# r10_328_1284.net
KiCad netlist of a schematic drawn in EAGLE
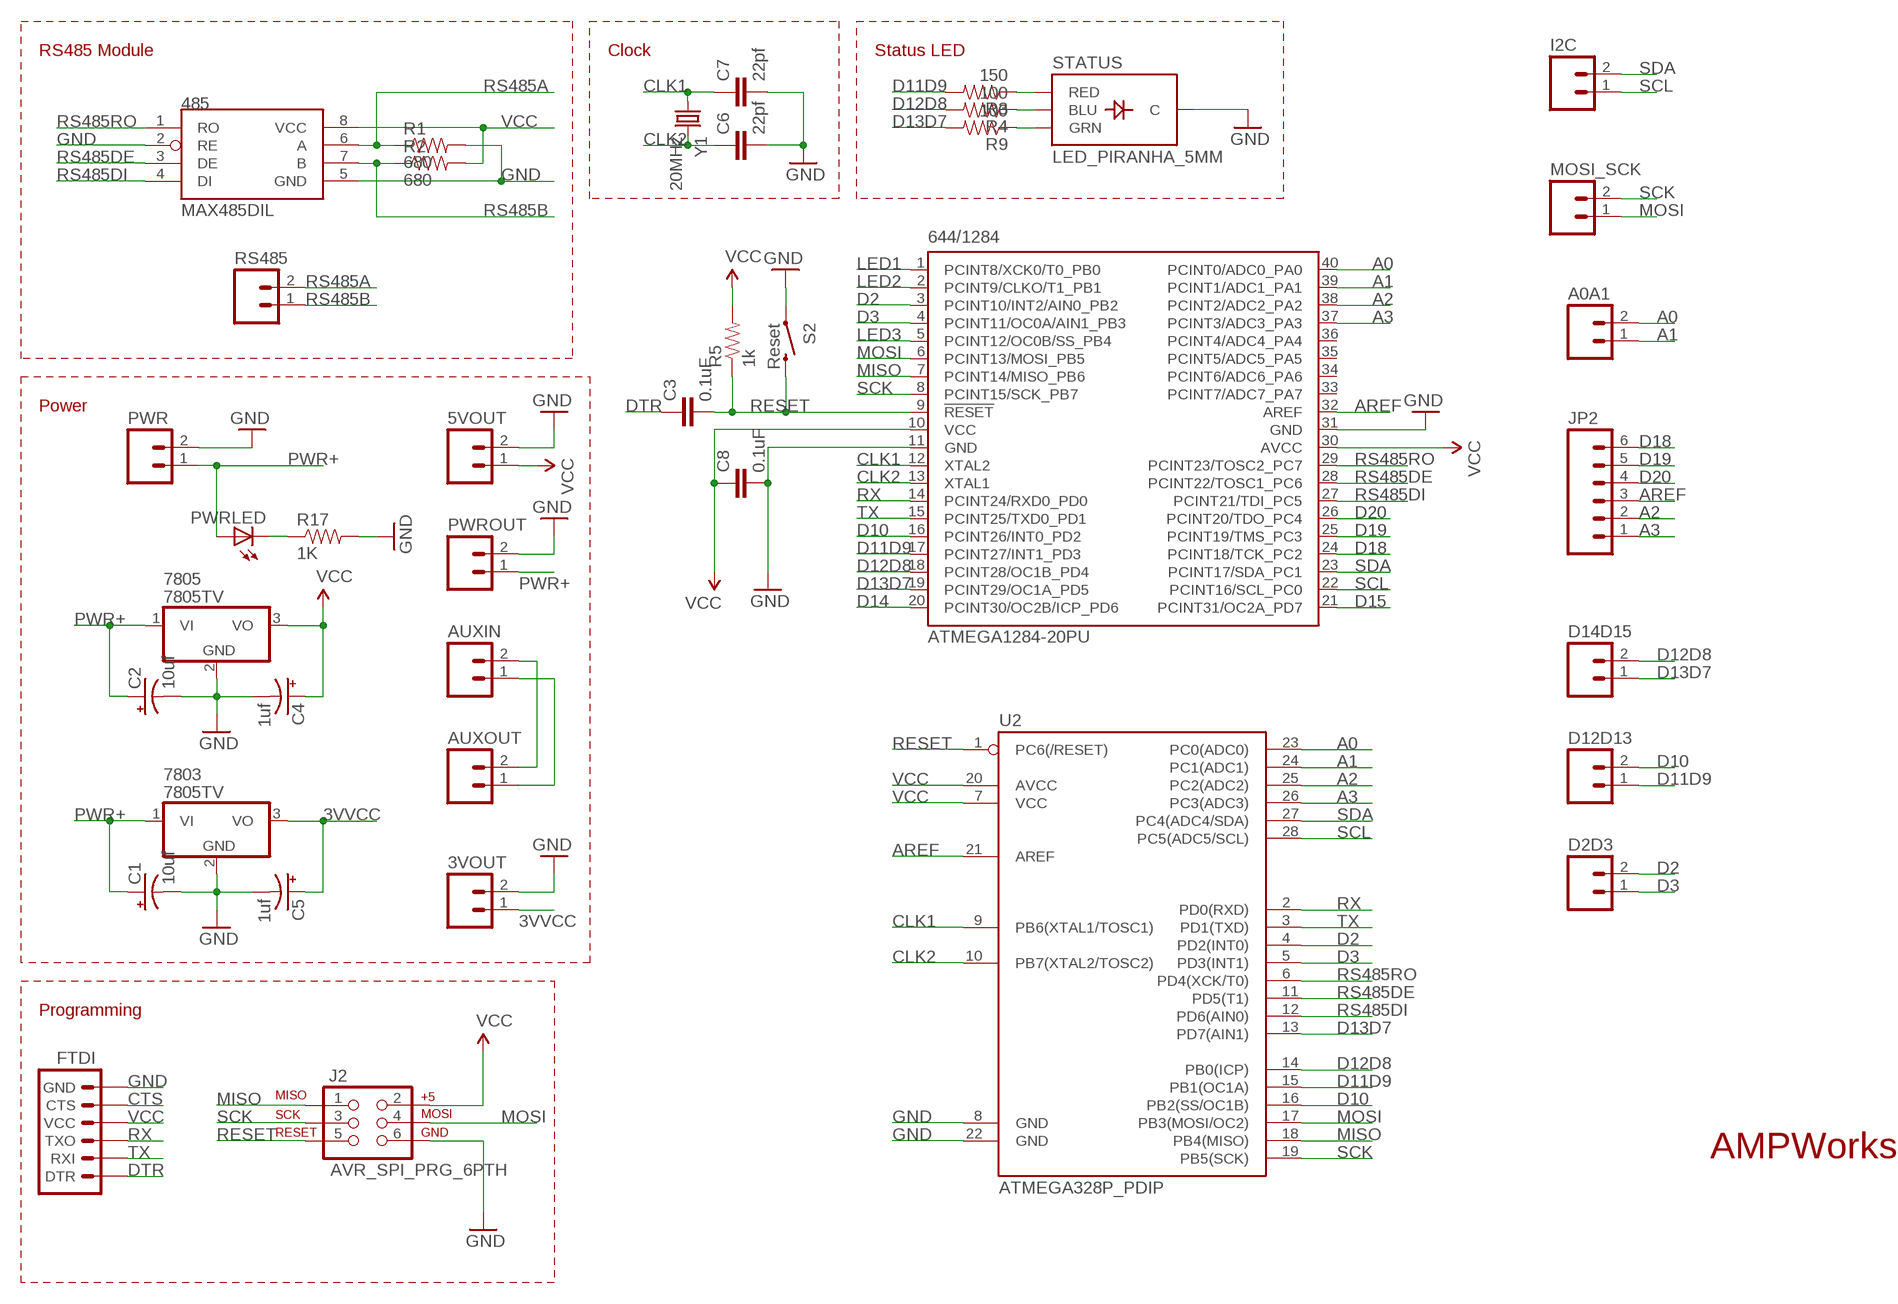
[diagram p0: schematic, sheet 1]

(export (version "E")
  (design (tool "Eeschema 10.0.6"))
  (components
    (comp (ref "3VOUT")
      (value "M025MM")
      (footprint "eagle-import:SCREWTERMINAL-5MM-2")
      (libsource (lib "eagle-import") (part "M025MM"))
    )
    (comp (ref "5VOUT")
      (value "M025MM")
      (footprint "eagle-import:SCREWTERMINAL-5MM-2")
      (libsource (lib "eagle-import") (part "M025MM"))
    )
    (comp (ref "485")
      (value "MAX485DIL")
      (footprint "eagle-import:DIL08")
      (libsource (lib "eagle-import") (part "MAX485DIL"))
    )
    (comp (ref "644/1284")
      (value "ATMEGA1284-20PU")
      (footprint "eagle-import:DIL40")
      (fields (field (name "MPN") "ATMEGA644-20PU"))
      (libsource (lib "eagle-import") (part "ATMEGA644-PU20"))
    )
    (comp (ref "7803")
      (value "7805TV")
      (footprint "eagle-import:TO220V")
      (libsource (lib "eagle-import") (part "78TV05"))
    )
    (comp (ref "7805")
      (value "7805TV")
      (footprint "eagle-import:TO220V")
      (libsource (lib "eagle-import") (part "78TV05"))
    )
    (comp (ref "A0A1")
      (value "M025MM")
      (footprint "eagle-import:SCREWTERMINAL-5MM-2")
      (libsource (lib "eagle-import") (part "M025MM"))
    )
    (comp (ref "AUXIN")
      (value "M025MM")
      (footprint "eagle-import:SCREWTERMINAL-5MM-2")
      (libsource (lib "eagle-import") (part "M025MM"))
    )
    (comp (ref "AUXOUT")
      (value "M025MM")
      (footprint "eagle-import:SCREWTERMINAL-5MM-2")
      (libsource (lib "eagle-import") (part "M025MM"))
    )
    (comp (ref "C1")
      (value "10uf")
      (footprint "eagle-import:CPOL-RADIAL-10UF-25V")
      (libsource (lib "eagle-import") (part "CAP_POLPTH2"))
    )
    (comp (ref "C2")
      (value "10uf")
      (footprint "eagle-import:CPOL-RADIAL-10UF-25V")
      (libsource (lib "eagle-import") (part "CAP_POLPTH2"))
    )
    (comp (ref "C3")
      (value "0.1uF")
      (footprint "eagle-import:CAP-PTH-SMALL")
      (libsource (lib "eagle-import") (part "CAPPTH"))
    )
    (comp (ref "C4")
      (value "1uf")
      (footprint "eagle-import:CPOL-RADIAL-10UF-25V")
      (libsource (lib "eagle-import") (part "CAP_POLPTH2"))
    )
    (comp (ref "C5")
      (value "1uf")
      (footprint "eagle-import:CPOL-RADIAL-10UF-25V")
      (libsource (lib "eagle-import") (part "CAP_POLPTH2"))
    )
    (comp (ref "C6")
      (value "22pf")
      (footprint "eagle-import:CAP-PTH-SMALL")
      (libsource (lib "eagle-import") (part "CAPPTH"))
    )
    (comp (ref "C7")
      (value "22pf")
      (footprint "eagle-import:CAP-PTH-SMALL")
      (libsource (lib "eagle-import") (part "CAPPTH"))
    )
    (comp (ref "C8")
      (value "0.1uF")
      (footprint "eagle-import:CAP-PTH-SMALL")
      (libsource (lib "eagle-import") (part "CAPPTH"))
    )
    (comp (ref "D2D3")
      (value "M025MM")
      (footprint "eagle-import:SCREWTERMINAL-5MM-2")
      (libsource (lib "eagle-import") (part "M025MM"))
    )
    (comp (ref "D12D13")
      (value "M025MM")
      (footprint "eagle-import:SCREWTERMINAL-5MM-2")
      (libsource (lib "eagle-import") (part "M025MM"))
    )
    (comp (ref "D14D15")
      (value "M025MM")
      (footprint "eagle-import:SCREWTERMINAL-5MM-2")
      (libsource (lib "eagle-import") (part "M025MM"))
    )
    (comp (ref "FTDI")
      (value "ARDUINO_SERIAL_PROGRAMPTH")
      (footprint "eagle-import:1X06")
      (libsource (lib "eagle-import") (part "ARDUINO_SERIAL_PROGRAMPTH"))
    )
    (comp (ref "I2C")
      (value "M025MM")
      (footprint "eagle-import:SCREWTERMINAL-5MM-2")
      (libsource (lib "eagle-import") (part "M025MM"))
    )
    (comp (ref "J2")
      (value "AVR_SPI_PRG_6PTH")
      (footprint "eagle-import:2X3")
      (libsource (lib "eagle-import") (part "AVR_SPI_PRG_6PTH"))
    )
    (comp (ref "JP2")
      (value "M06NO_SILK")
      (footprint "eagle-import:1X06_NO_SILK")
      (libsource (lib "eagle-import") (part "M06NO_SILK"))
    )
    (comp (ref "MOSI_SCK")
      (value "M025MM")
      (footprint "eagle-import:SCREWTERMINAL-5MM-2")
      (libsource (lib "eagle-import") (part "M025MM"))
    )
    (comp (ref "PWR")
      (value "M025MM")
      (footprint "eagle-import:SCREWTERMINAL-5MM-2")
      (libsource (lib "eagle-import") (part "M025MM"))
    )
    (comp (ref "PWRLED")
      (value "LED5MM")
      (footprint "eagle-import:LED5MM")
      (libsource (lib "eagle-import") (part "LED5MM"))
    )
    (comp (ref "PWROUT")
      (value "M025MM")
      (footprint "eagle-import:SCREWTERMINAL-5MM-2")
      (libsource (lib "eagle-import") (part "M025MM"))
    )
    (comp (ref "R1")
      (value "680")
      (footprint "eagle-import:AXIAL-0.4")
      (libsource (lib "eagle-import") (part "SparkFun-Resistors_RESISTORPTH-1/4W"))
    )
    (comp (ref "R2")
      (value "680")
      (footprint "eagle-import:AXIAL-0.4")
      (libsource (lib "eagle-import") (part "SparkFun-Resistors_RESISTORPTH-1/4W"))
    )
    (comp (ref "R3")
      (value "150")
      (footprint "eagle-import:AXIAL-0.4")
      (libsource (lib "eagle-import") (part "RESISTORPTH-1/4W"))
    )
    (comp (ref "R4")
      (value "100")
      (footprint "eagle-import:AXIAL-0.4")
      (libsource (lib "eagle-import") (part "RESISTORPTH-1/4W"))
    )
    (comp (ref "R5")
      (value "1k")
      (footprint "eagle-import:AXIAL-0.4")
      (libsource (lib "eagle-import") (part "RESISTORPTH-1/4W"))
    )
    (comp (ref "R9")
      (value "100")
      (footprint "eagle-import:AXIAL-0.4")
      (libsource (lib "eagle-import") (part "RESISTORPTH-1/4W"))
    )
    (comp (ref "R17")
      (value "1K")
      (footprint "eagle-import:AXIAL-0.4")
      (libsource (lib "eagle-import") (part "SparkFun-Resistors_RESISTORPTH-1/4W"))
    )
    (comp (ref "RS485")
      (value "M025MM")
      (footprint "eagle-import:SCREWTERMINAL-5MM-2")
      (libsource (lib "eagle-import") (part "M025MM"))
    )
    (comp (ref "S2")
      (value "Reset")
      (footprint "eagle-import:TACTILE_SWITCH_SMD")
      (libsource (lib "eagle-import") (part "SWITCH-MOMENTARY-2SMD"))
    )
    (comp (ref "STATUS")
      (value "LED_PIRANHA_5MM")
      (footprint "eagle-import:LED_PIRANHA_5MM")
      (libsource (lib "eagle-import") (part "LED_PIRANHA_5MM"))
    )
    (comp (ref "U2")
      (value "ATMEGA328P_PDIP")
      (footprint "eagle-import:DIL28-3")
      (libsource (lib "eagle-import") (part "ATMEGA328P_PDIP"))
    )
    (comp (ref "Y1")
      (value "20MHz")
      (footprint "eagle-import:HC49US")
      (libsource (lib "eagle-import") (part "CRYSTALHC49US"))
    )
  )
  (nets
    (net (code "1") (name "/3VVCC") (class "Default")
      (node (ref "3VOUT") (pin "1") (pinfunction "1_1") (pintype "passive"))
      (node (ref "7803") (pin "3") (pinfunction "VO_3") (pintype "passive"))
      (node (ref "C5") (pin "1") (pinfunction "+_1") (pintype "passive"))
    )
    (net (code "2") (name "/A0") (class "Default")
      (node (ref "644/1284") (pin "40") (pinfunction "PCINT0/ADC0_PA0_40") (pintype "bidirectional"))
      (node (ref "A0A1") (pin "2") (pinfunction "2_2") (pintype "passive"))
      (node (ref "U2") (pin "23") (pinfunction "PC0(ADC0)_23") (pintype "bidirectional"))
    )
    (net (code "3") (name "/A1") (class "Default")
      (node (ref "644/1284") (pin "39") (pinfunction "PCINT1/ADC1_PA1_39") (pintype "bidirectional"))
      (node (ref "A0A1") (pin "1") (pinfunction "1_1") (pintype "passive"))
      (node (ref "U2") (pin "24") (pinfunction "PC1(ADC1)_24") (pintype "bidirectional"))
    )
    (net (code "4") (name "/A2") (class "Default")
      (node (ref "644/1284") (pin "38") (pinfunction "PCINT2/ADC2_PA2_38") (pintype "bidirectional"))
      (node (ref "JP2") (pin "2") (pinfunction "2_2") (pintype "passive"))
      (node (ref "U2") (pin "25") (pinfunction "PC2(ADC2)_25") (pintype "bidirectional"))
    )
    (net (code "5") (name "/A3") (class "Default")
      (node (ref "644/1284") (pin "37") (pinfunction "PCINT3/ADC3_PA3_37") (pintype "bidirectional"))
      (node (ref "JP2") (pin "1") (pinfunction "1_1") (pintype "passive"))
      (node (ref "U2") (pin "26") (pinfunction "PC3(ADC3)_26") (pintype "bidirectional"))
    )
    (net (code "6") (name "/AREF") (class "Default")
      (node (ref "644/1284") (pin "32") (pinfunction "AREF_32") (pintype "passive"))
      (node (ref "JP2") (pin "3") (pinfunction "3_3") (pintype "passive"))
      (node (ref "U2") (pin "21") (pinfunction "AREF_21") (pintype "bidirectional"))
    )
    (net (code "7") (name "/CLK1") (class "Default")
      (node (ref "644/1284") (pin "12") (pinfunction "XTAL2_12") (pintype "output"))
      (node (ref "C7") (pin "1") (pinfunction "1_1") (pintype "passive"))
      (node (ref "U2") (pin "9") (pinfunction "PB6(XTAL1/TOSC1)_9") (pintype "bidirectional"))
      (node (ref "Y1") (pin "1") (pinfunction "1_1") (pintype "passive"))
    )
    (net (code "8") (name "/CLK2") (class "Default")
      (node (ref "644/1284") (pin "13") (pinfunction "XTAL1_13") (pintype "input"))
      (node (ref "C6") (pin "1") (pinfunction "1_1") (pintype "passive"))
      (node (ref "U2") (pin "10") (pinfunction "PB7(XTAL2/TOSC2)_10") (pintype "bidirectional"))
      (node (ref "Y1") (pin "2") (pinfunction "2_2") (pintype "passive"))
    )
    (net (code "9") (name "/CTS") (class "Default")
      (node (ref "FTDI") (pin "CTS") (pinfunction "CTS_CTS") (pintype "passive"))
    )
    (net (code "10") (name "/D2") (class "Default")
      (node (ref "644/1284") (pin "3") (pinfunction "PCINT10/INT2/AIN0_PB2_3") (pintype "bidirectional"))
      (node (ref "D2D3") (pin "2") (pinfunction "2_2") (pintype "passive"))
      (node (ref "U2") (pin "4") (pinfunction "PD2(INT0)_4") (pintype "bidirectional"))
    )
    (net (code "11") (name "/D3") (class "Default")
      (node (ref "644/1284") (pin "4") (pinfunction "PCINT11/OC0A/AIN1_PB3_4") (pintype "bidirectional"))
      (node (ref "D2D3") (pin "1") (pinfunction "1_1") (pintype "passive"))
      (node (ref "U2") (pin "5") (pinfunction "PD3(INT1)_5") (pintype "bidirectional"))
    )
    (net (code "12") (name "/D10") (class "Default")
      (node (ref "644/1284") (pin "16") (pinfunction "PCINT26/INT0_PD2_16") (pintype "bidirectional"))
      (node (ref "D12D13") (pin "2") (pinfunction "2_2") (pintype "passive"))
      (node (ref "U2") (pin "16") (pinfunction "PB2(SS/OC1B)_16") (pintype "bidirectional"))
    )
    (net (code "13") (name "/D11D9") (class "Default")
      (node (ref "644/1284") (pin "17") (pinfunction "PCINT27/INT1_PD3_17") (pintype "bidirectional"))
      (node (ref "D12D13") (pin "1") (pinfunction "1_1") (pintype "passive"))
      (node (ref "R3") (pin "P$2") (pinfunction "2_P$2") (pintype "passive"))
      (node (ref "U2") (pin "15") (pinfunction "PB1(OC1A)_15") (pintype "bidirectional"))
    )
    (net (code "14") (name "/D12D8") (class "Default")
      (node (ref "644/1284") (pin "18") (pinfunction "PCINT28/OC1B_PD4_18") (pintype "bidirectional"))
      (node (ref "D14D15") (pin "2") (pinfunction "2_2") (pintype "passive"))
      (node (ref "R4") (pin "P$2") (pinfunction "2_P$2") (pintype "passive"))
      (node (ref "U2") (pin "14") (pinfunction "PB0(ICP)_14") (pintype "bidirectional"))
    )
    (net (code "15") (name "/D13D7") (class "Default")
      (node (ref "644/1284") (pin "19") (pinfunction "PCINT29/OC1A_PD5_19") (pintype "bidirectional"))
      (node (ref "D14D15") (pin "1") (pinfunction "1_1") (pintype "passive"))
      (node (ref "R9") (pin "P$2") (pinfunction "2_P$2") (pintype "passive"))
      (node (ref "U2") (pin "13") (pinfunction "PD7(AIN1)_13") (pintype "bidirectional"))
    )
    (net (code "16") (name "/D14") (class "Default")
      (node (ref "644/1284") (pin "20") (pinfunction "PCINT30/OC2B/ICP_PD6_20") (pintype "bidirectional"))
    )
    (net (code "17") (name "/D15") (class "Default")
      (node (ref "644/1284") (pin "21") (pinfunction "PCINT31/OC2A_PD7_21") (pintype "bidirectional"))
    )
    (net (code "18") (name "/D18") (class "Default")
      (node (ref "644/1284") (pin "24") (pinfunction "PCINT18/TCK_PC2_24") (pintype "bidirectional"))
      (node (ref "JP2") (pin "6") (pinfunction "6_6") (pintype "passive"))
    )
    (net (code "19") (name "/D19") (class "Default")
      (node (ref "644/1284") (pin "25") (pinfunction "PCINT19/TMS_PC3_25") (pintype "bidirectional"))
      (node (ref "JP2") (pin "5") (pinfunction "5_5") (pintype "passive"))
    )
    (net (code "20") (name "/D20") (class "Default")
      (node (ref "644/1284") (pin "26") (pinfunction "PCINT20/TDO_PC4_26") (pintype "bidirectional"))
      (node (ref "JP2") (pin "4") (pinfunction "4_4") (pintype "passive"))
    )
    (net (code "21") (name "/DTR") (class "Default")
      (node (ref "C3") (pin "1") (pinfunction "1_1") (pintype "passive"))
      (node (ref "FTDI") (pin "DTR") (pinfunction "DTR_DTR") (pintype "passive"))
    )
    (net (code "22") (name "/LED1") (class "Default")
      (node (ref "644/1284") (pin "1") (pinfunction "PCINT8/XCK0/T0_PB0_1") (pintype "bidirectional"))
    )
    (net (code "23") (name "/LED2") (class "Default")
      (node (ref "644/1284") (pin "2") (pinfunction "PCINT9/CLKO/T1_PB1_2") (pintype "bidirectional"))
    )
    (net (code "24") (name "/LED3") (class "Default")
      (node (ref "644/1284") (pin "5") (pinfunction "PCINT12/OC0B/SS_PB4_5") (pintype "bidirectional"))
    )
    (net (code "25") (name "/MISO") (class "Default")
      (node (ref "644/1284") (pin "7") (pinfunction "PCINT14/MISO_PB6_7") (pintype "bidirectional"))
      (node (ref "J2") (pin "1") (pinfunction "1_1") (pintype "passive"))
      (node (ref "U2") (pin "18") (pinfunction "PB4(MISO)_18") (pintype "bidirectional"))
    )
    (net (code "26") (name "/MOSI") (class "Default")
      (node (ref "644/1284") (pin "6") (pinfunction "PCINT13/MOSI_PB5_6") (pintype "bidirectional"))
      (node (ref "J2") (pin "4") (pinfunction "4_4") (pintype "passive"))
      (node (ref "MOSI_SCK") (pin "1") (pinfunction "1_1") (pintype "passive"))
      (node (ref "U2") (pin "17") (pinfunction "PB3(MOSI/OC2)_17") (pintype "bidirectional"))
    )
    (net (code "27") (name "/PWR+") (class "Default")
      (node (ref "7803") (pin "1") (pinfunction "VI_1") (pintype "input"))
      (node (ref "7805") (pin "1") (pinfunction "VI_1") (pintype "input"))
      (node (ref "C1") (pin "1") (pinfunction "+_1") (pintype "passive"))
      (node (ref "C2") (pin "1") (pinfunction "+_1") (pintype "passive"))
      (node (ref "PWR") (pin "1") (pinfunction "1_1") (pintype "passive"))
      (node (ref "PWRLED") (pin "A") (pinfunction "A_A") (pintype "passive"))
      (node (ref "PWROUT") (pin "1") (pinfunction "1_1") (pintype "passive"))
    )
    (net (code "28") (name "/RESET") (class "Default")
      (node (ref "644/1284") (pin "9") (pinfunction "~{RESET}_9") (pintype "input"))
      (node (ref "C3") (pin "2") (pinfunction "2_2") (pintype "passive"))
      (node (ref "J2") (pin "5") (pinfunction "5_5") (pintype "passive"))
      (node (ref "R5") (pin "P$1") (pinfunction "1_P$1") (pintype "passive"))
      (node (ref "S2") (pin "3") (pinfunction "2_3") (pintype "passive"))
      (node (ref "U2") (pin "1") (pinfunction "PC6(/RESET)_1") (pintype "bidirectional"))
    )
    (net (code "29") (name "/RS485A") (class "Default")
      (node (ref "485") (pin "6") (pinfunction "A_6") (pintype "bidirectional"))
      (node (ref "R1") (pin "P$1") (pinfunction "1_P$1") (pintype "passive"))
      (node (ref "RS485") (pin "2") (pinfunction "2_2") (pintype "passive"))
    )
    (net (code "30") (name "/RS485B") (class "Default")
      (node (ref "485") (pin "7") (pinfunction "B_7") (pintype "bidirectional"))
      (node (ref "R2") (pin "P$1") (pinfunction "1_P$1") (pintype "passive"))
      (node (ref "RS485") (pin "1") (pinfunction "1_1") (pintype "passive"))
    )
    (net (code "31") (name "/RS485DE") (class "Default")
      (node (ref "485") (pin "3") (pinfunction "DE_3") (pintype "bidirectional"))
      (node (ref "644/1284") (pin "28") (pinfunction "PCINT22/TOSC1_PC6_28") (pintype "bidirectional"))
      (node (ref "U2") (pin "11") (pinfunction "PD5(T1)_11") (pintype "bidirectional"))
    )
    (net (code "32") (name "/RS485DI") (class "Default")
      (node (ref "485") (pin "4") (pinfunction "DI_4") (pintype "bidirectional"))
      (node (ref "644/1284") (pin "27") (pinfunction "PCINT21/TDI_PC5_27") (pintype "bidirectional"))
      (node (ref "U2") (pin "12") (pinfunction "PD6(AIN0)_12") (pintype "bidirectional"))
    )
    (net (code "33") (name "/RS485RO") (class "Default")
      (node (ref "485") (pin "1") (pinfunction "RO_1") (pintype "bidirectional"))
      (node (ref "644/1284") (pin "29") (pinfunction "PCINT23/TOSC2_PC7_29") (pintype "bidirectional"))
      (node (ref "U2") (pin "6") (pinfunction "PD4(XCK/T0)_6") (pintype "bidirectional"))
    )
    (net (code "34") (name "/RX") (class "Default")
      (node (ref "644/1284") (pin "14") (pinfunction "PCINT24/RXD0_PD0_14") (pintype "bidirectional"))
      (node (ref "FTDI") (pin "TXO") (pinfunction "TXO_TXO") (pintype "passive"))
      (node (ref "U2") (pin "2") (pinfunction "PD0(RXD)_2") (pintype "bidirectional"))
    )
    (net (code "35") (name "/SCK") (class "Default")
      (node (ref "644/1284") (pin "8") (pinfunction "PCINT15/SCK_PB7_8") (pintype "bidirectional"))
      (node (ref "J2") (pin "3") (pinfunction "3_3") (pintype "passive"))
      (node (ref "MOSI_SCK") (pin "2") (pinfunction "2_2") (pintype "passive"))
      (node (ref "U2") (pin "19") (pinfunction "PB5(SCK)_19") (pintype "bidirectional"))
    )
    (net (code "36") (name "/SCL") (class "Default")
      (node (ref "644/1284") (pin "22") (pinfunction "PCINT16/SCL_PC0_22") (pintype "bidirectional"))
      (node (ref "I2C") (pin "1") (pinfunction "1_1") (pintype "passive"))
      (node (ref "U2") (pin "28") (pinfunction "PC5(ADC5/SCL)_28") (pintype "bidirectional"))
    )
    (net (code "37") (name "/SDA") (class "Default")
      (node (ref "644/1284") (pin "23") (pinfunction "PCINT17/SDA_PC1_23") (pintype "bidirectional"))
      (node (ref "I2C") (pin "2") (pinfunction "2_2") (pintype "passive"))
      (node (ref "U2") (pin "27") (pinfunction "PC4(ADC4/SDA)_27") (pintype "bidirectional"))
    )
    (net (code "38") (name "/TX") (class "Default")
      (node (ref "644/1284") (pin "15") (pinfunction "PCINT25/TXD0_PD1_15") (pintype "bidirectional"))
      (node (ref "FTDI") (pin "RXI") (pinfunction "RXI_RXI") (pintype "passive"))
      (node (ref "U2") (pin "3") (pinfunction "PD1(TXD)_3") (pintype "bidirectional"))
    )
    (net (code "39") (name "GND") (class "Default")
      (node (ref "3VOUT") (pin "2") (pinfunction "2_2") (pintype "passive"))
      (node (ref "485") (pin "2") (pinfunction "RE_2") (pintype "bidirectional"))
      (node (ref "485") (pin "5") (pinfunction "GND_5") (pintype "bidirectional"))
      (node (ref "5VOUT") (pin "2") (pinfunction "2_2") (pintype "passive"))
      (node (ref "644/1284") (pin "11") (pinfunction "GND_11") (pintype "power_in"))
      (node (ref "644/1284") (pin "31") (pinfunction "GND_31") (pintype "power_in"))
      (node (ref "7803") (pin "2") (pinfunction "GND_2") (pintype "passive"))
      (node (ref "7805") (pin "2") (pinfunction "GND_2") (pintype "passive"))
      (node (ref "C1") (pin "2") (pinfunction "-_2") (pintype "passive"))
      (node (ref "C2") (pin "2") (pinfunction "-_2") (pintype "passive"))
      (node (ref "C4") (pin "2") (pinfunction "-_2") (pintype "passive"))
      (node (ref "C5") (pin "2") (pinfunction "-_2") (pintype "passive"))
      (node (ref "C6") (pin "2") (pinfunction "2_2") (pintype "passive"))
      (node (ref "C7") (pin "2") (pinfunction "2_2") (pintype "passive"))
      (node (ref "C8") (pin "2") (pinfunction "2_2") (pintype "passive"))
      (node (ref "FTDI") (pin "GND") (pinfunction "GND_GND") (pintype "passive"))
      (node (ref "J2") (pin "6") (pinfunction "6_6") (pintype "passive"))
      (node (ref "PWR") (pin "2") (pinfunction "2_2") (pintype "passive"))
      (node (ref "PWROUT") (pin "2") (pinfunction "2_2") (pintype "passive"))
      (node (ref "R1") (pin "P$2") (pinfunction "2_P$2") (pintype "passive"))
      (node (ref "R17") (pin "P$2") (pinfunction "2_P$2") (pintype "passive"))
      (node (ref "S2") (pin "1") (pinfunction "1_1") (pintype "passive"))
      (node (ref "STATUS") (pin "-") (pinfunction "C_-") (pintype "bidirectional"))
      (node (ref "U2") (pin "22") (pinfunction "GND_22") (pintype "bidirectional"))
      (node (ref "U2") (pin "8") (pinfunction "GND_8") (pintype "bidirectional"))
    )
    (net (code "40") (name "Net-(AUXIN-Pad1)") (class "Default")
      (node (ref "AUXIN") (pin "1") (pinfunction "1_1") (pintype "passive"))
      (node (ref "AUXOUT") (pin "1") (pinfunction "1_1") (pintype "passive"))
    )
    (net (code "41") (name "Net-(AUXIN-Pad2)") (class "Default")
      (node (ref "AUXIN") (pin "2") (pinfunction "2_2") (pintype "passive"))
      (node (ref "AUXOUT") (pin "2") (pinfunction "2_2") (pintype "passive"))
    )
    (net (code "42") (name "Net-(PWRLED-C)") (class "Default")
      (node (ref "PWRLED") (pin "K") (pinfunction "C_K") (pintype "passive"))
      (node (ref "R17") (pin "P$1") (pinfunction "1_P$1") (pintype "passive"))
    )
    (net (code "43") (name "Net-(R3-1)") (class "Default")
      (node (ref "R3") (pin "P$1") (pinfunction "1_P$1") (pintype "passive"))
      (node (ref "STATUS") (pin "R") (pinfunction "RED_R") (pintype "bidirectional"))
    )
    (net (code "44") (name "Net-(R4-1)") (class "Default")
      (node (ref "R4") (pin "P$1") (pinfunction "1_P$1") (pintype "passive"))
      (node (ref "STATUS") (pin "B") (pinfunction "BLU_B") (pintype "bidirectional"))
    )
    (net (code "45") (name "Net-(R9-1)") (class "Default")
      (node (ref "R9") (pin "P$1") (pinfunction "1_P$1") (pintype "passive"))
      (node (ref "STATUS") (pin "G") (pinfunction "GRN_G") (pintype "bidirectional"))
    )
    (net (code "46") (name "VCC") (class "Default")
      (node (ref "485") (pin "8") (pinfunction "VCC_8") (pintype "bidirectional"))
      (node (ref "5VOUT") (pin "1") (pinfunction "1_1") (pintype "passive"))
      (node (ref "644/1284") (pin "10") (pinfunction "VCC_10") (pintype "power_in"))
      (node (ref "644/1284") (pin "30") (pinfunction "AVCC_30") (pintype "power_in"))
      (node (ref "7805") (pin "3") (pinfunction "VO_3") (pintype "passive"))
      (node (ref "C4") (pin "1") (pinfunction "+_1") (pintype "passive"))
      (node (ref "C8") (pin "1") (pinfunction "1_1") (pintype "passive"))
      (node (ref "FTDI") (pin "VCC") (pinfunction "VCC_VCC") (pintype "passive"))
      (node (ref "J2") (pin "2") (pinfunction "2_2") (pintype "passive"))
      (node (ref "R2") (pin "P$2") (pinfunction "2_P$2") (pintype "passive"))
      (node (ref "R5") (pin "P$2") (pinfunction "2_P$2") (pintype "passive"))
      (node (ref "U2") (pin "20") (pinfunction "AVCC_20") (pintype "bidirectional"))
      (node (ref "U2") (pin "7") (pinfunction "VCC_7") (pintype "bidirectional"))
    )
    (net (code "47") (name "unconnected-(644/1284-PCINT4{slash}ADC4_PA4-Pad36)") (class "Default")
      (node (ref "644/1284") (pin "36") (pinfunction "PCINT4/ADC4_PA4_36") (pintype "bidirectional"))
    )
    (net (code "48") (name "unconnected-(644/1284-PCINT5{slash}ADC5_PA5-Pad35)") (class "Default")
      (node (ref "644/1284") (pin "35") (pinfunction "PCINT5/ADC5_PA5_35") (pintype "bidirectional"))
    )
    (net (code "49") (name "unconnected-(644/1284-PCINT6{slash}ADC6_PA6-Pad34)") (class "Default")
      (node (ref "644/1284") (pin "34") (pinfunction "PCINT6/ADC6_PA6_34") (pintype "bidirectional"))
    )
    (net (code "50") (name "unconnected-(644/1284-PCINT7{slash}ADC7_PA7-Pad33)") (class "Default")
      (node (ref "644/1284") (pin "33") (pinfunction "PCINT7/ADC7_PA7_33") (pintype "bidirectional"))
    )
  )
)
